# ESP8266to32.net
KiCad netlist of a schematic drawn in Altium Designer
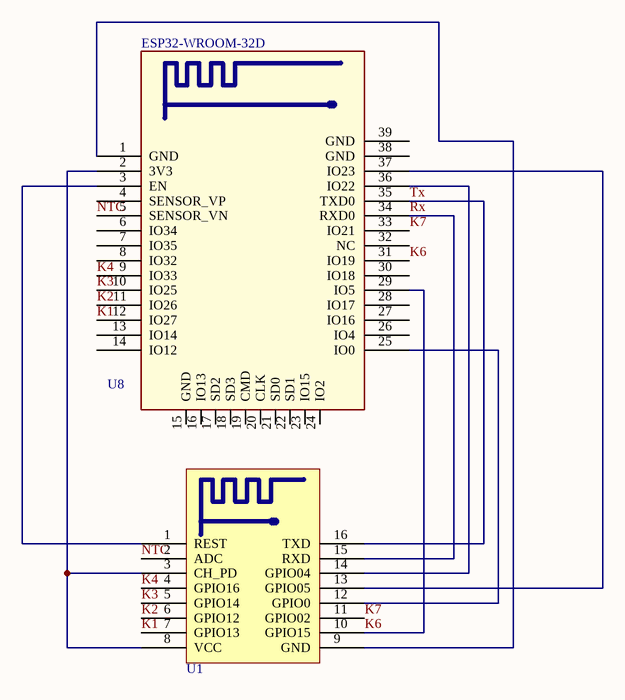
[diagram p0: ESP8266to32.SchDoc]

(export (version "E")
  (design (tool "Eeschema 10.0.6"))
  (components
    (comp (ref "U1") (value "ESP-8266") (footprint "ESP_12E") (libsource (lib "msb") (part "ESP-8266")))
    (comp (ref "U8")
      (value "ESP32-WROOM-32D")
      (footprint "esp32 WROOM-L")
      (description "IC: SoC; GPIO, I2C, I2S, IR, SD, SDIO, SPI, UART; 2.7Ã·3.6VDC; 20dBm")
      (fields (field (name "MF") "Espressif Systems"))
      (libsource (lib "msb") (part "ESP32-WROOM-32D"))
    )
  )
  (nets
    (net (code "1") (name "/K1") (class "Default")
      (node (ref "U1") (pin "7") (pinfunction "GPIO13_7") (pintype "passive"))
      (node (ref "U8") (pin "12") (pinfunction "IO27_12") (pintype "passive"))
    )
    (net (code "2") (name "/K2") (class "Default")
      (node (ref "U1") (pin "6") (pinfunction "GPIO12_6") (pintype "passive"))
      (node (ref "U8") (pin "11") (pinfunction "IO26_11") (pintype "passive"))
    )
    (net (code "3") (name "/K3") (class "Default")
      (node (ref "U1") (pin "5") (pinfunction "GPIO14_5") (pintype "passive"))
      (node (ref "U8") (pin "10") (pinfunction "IO25_10") (pintype "passive"))
    )
    (net (code "4") (name "/K4") (class "Default")
      (node (ref "U1") (pin "4") (pinfunction "GPIO16_4") (pintype "passive"))
      (node (ref "U8") (pin "9") (pinfunction "IO33_9") (pintype "passive"))
    )
    (net (code "5") (name "/K6") (class "Default")
      (node (ref "U1") (pin "10") (pinfunction "GPIO15_10") (pintype "passive"))
      (node (ref "U8") (pin "29") (pinfunction "IO5_29") (pintype "passive"))
      (node (ref "U8") (pin "31") (pinfunction "IO19_31") (pintype "passive"))
    )
    (net (code "6") (name "/K7") (class "Default")
      (node (ref "U1") (pin "11") (pinfunction "GPIO02_11") (pintype "passive"))
      (node (ref "U8") (pin "33") (pinfunction "IO21_33") (pintype "passive"))
    )
    (net (code "7") (name "/NTC") (class "Default")
      (node (ref "U1") (pin "2") (pinfunction "ADC_2") (pintype "passive"))
      (node (ref "U8") (pin "5") (pinfunction "SENSOR_VN_5") (pintype "passive"))
    )
    (net (code "8") (name "/Rx") (class "Default")
      (node (ref "U1") (pin "15") (pinfunction "RXD_15") (pintype "passive"))
      (node (ref "U8") (pin "34") (pinfunction "RXD0_34") (pintype "passive"))
    )
    (net (code "9") (name "/Tx") (class "Default")
      (node (ref "U1") (pin "16") (pinfunction "TXD_16") (pintype "passive"))
      (node (ref "U8") (pin "35") (pinfunction "TXD0_35") (pintype "passive"))
    )
    (net (code "10") (name "Net-(U1-CH_PD)") (class "Default")
      (node (ref "U1") (pin "3") (pinfunction "CH_PD_3") (pintype "passive"))
      (node (ref "U1") (pin "8") (pinfunction "VCC_8") (pintype "power_in"))
      (node (ref "U8") (pin "2") (pinfunction "3V3_2") (pintype "power_in"))
    )
    (net (code "11") (name "Net-(U1-GND)") (class "Default")
      (node (ref "U1") (pin "9") (pinfunction "GND_9") (pintype "power_in"))
      (node (ref "U8") (pin "1") (pinfunction "GND_1") (pintype "power_in"))
    )
    (net (code "12") (name "Net-(U1-GPIO0)") (class "Default")
      (node (ref "U1") (pin "12") (pinfunction "GPIO0_12") (pintype "passive"))
      (node (ref "U8") (pin "25") (pinfunction "IO0_25") (pintype "passive"))
    )
    (net (code "13") (name "Net-(U1-GPIO04)") (class "Default")
      (node (ref "U1") (pin "14") (pinfunction "GPIO04_14") (pintype "passive"))
      (node (ref "U8") (pin "36") (pinfunction "IO22_36") (pintype "passive"))
    )
    (net (code "14") (name "Net-(U1-GPIO05)") (class "Default")
      (node (ref "U1") (pin "13") (pinfunction "GPIO05_13") (pintype "passive"))
      (node (ref "U8") (pin "37") (pinfunction "IO23_37") (pintype "passive"))
    )
    (net (code "15") (name "Net-(U1-REST)") (class "Default")
      (node (ref "U1") (pin "1") (pinfunction "REST_1") (pintype "passive"))
      (node (ref "U8") (pin "3") (pinfunction "EN_3") (pintype "passive"))
    )
    (net (code "16") (name "unconnected-(U8-CLK-Pad20)") (class "Default")
      (node (ref "U8") (pin "20") (pinfunction "CLK_20") (pintype "passive"))
    )
    (net (code "17") (name "unconnected-(U8-CMD-Pad19)") (class "Default")
      (node (ref "U8") (pin "19") (pinfunction "CMD_19") (pintype "passive"))
    )
    (net (code "18") (name "unconnected-(U8-GND-Pad15)") (class "Default")
      (node (ref "U8") (pin "15") (pinfunction "GND_15") (pintype "power_in"))
    )
    (net (code "19") (name "unconnected-(U8-GND-Pad38)") (class "Default")
      (node (ref "U8") (pin "38") (pinfunction "GND_38") (pintype "passive"))
    )
    (net (code "20") (name "unconnected-(U8-GND-Pad39)") (class "Default")
      (node (ref "U8") (pin "39") (pinfunction "GND_39") (pintype "power_in"))
    )
    (net (code "21") (name "unconnected-(U8-IO2-Pad24)") (class "Default")
      (node (ref "U8") (pin "24") (pinfunction "IO2_24") (pintype "passive"))
    )
    (net (code "22") (name "unconnected-(U8-IO4-Pad26)") (class "Default")
      (node (ref "U8") (pin "26") (pinfunction "IO4_26") (pintype "passive"))
    )
    (net (code "23") (name "unconnected-(U8-IO12-Pad14)") (class "Default")
      (node (ref "U8") (pin "14") (pinfunction "IO12_14") (pintype "passive"))
    )
    (net (code "24") (name "unconnected-(U8-IO13-Pad16)") (class "Default")
      (node (ref "U8") (pin "16") (pinfunction "IO13_16") (pintype "passive"))
    )
    (net (code "25") (name "unconnected-(U8-IO14-Pad13)") (class "Default")
      (node (ref "U8") (pin "13") (pinfunction "IO14_13") (pintype "passive"))
    )
    (net (code "26") (name "unconnected-(U8-IO15-Pad23)") (class "Default")
      (node (ref "U8") (pin "23") (pinfunction "IO15_23") (pintype "passive"))
    )
    (net (code "27") (name "unconnected-(U8-IO16-Pad27)") (class "Default")
      (node (ref "U8") (pin "27") (pinfunction "IO16_27") (pintype "passive"))
    )
    (net (code "28") (name "unconnected-(U8-IO17-Pad28)") (class "Default")
      (node (ref "U8") (pin "28") (pinfunction "IO17_28") (pintype "passive"))
    )
    (net (code "29") (name "unconnected-(U8-IO18-Pad30)") (class "Default")
      (node (ref "U8") (pin "30") (pinfunction "IO18_30") (pintype "passive"))
    )
    (net (code "30") (name "unconnected-(U8-IO32-Pad8)") (class "Default")
      (node (ref "U8") (pin "8") (pinfunction "IO32_8") (pintype "passive"))
    )
    (net (code "31") (name "unconnected-(U8-IO34-Pad6)") (class "Default")
      (node (ref "U8") (pin "6") (pinfunction "IO34_6") (pintype "passive"))
    )
    (net (code "32") (name "unconnected-(U8-IO35-Pad7)") (class "Default")
      (node (ref "U8") (pin "7") (pinfunction "IO35_7") (pintype "passive"))
    )
    (net (code "33") (name "unconnected-(U8-NC-Pad32)") (class "Default")
      (node (ref "U8") (pin "32") (pinfunction "NC_32") (pintype "passive"))
    )
    (net (code "34") (name "unconnected-(U8-SD0-Pad21)") (class "Default")
      (node (ref "U8") (pin "21") (pinfunction "SD0_21") (pintype "passive"))
    )
    (net (code "35") (name "unconnected-(U8-SD1-Pad22)") (class "Default")
      (node (ref "U8") (pin "22") (pinfunction "SD1_22") (pintype "passive"))
    )
    (net (code "36") (name "unconnected-(U8-SD2-Pad17)") (class "Default")
      (node (ref "U8") (pin "17") (pinfunction "SD2_17") (pintype "passive"))
    )
    (net (code "37") (name "unconnected-(U8-SD3-Pad18)") (class "Default")
      (node (ref "U8") (pin "18") (pinfunction "SD3_18") (pintype "passive"))
    )
    (net (code "38") (name "unconnected-(U8-SENSOR_VP-Pad4)") (class "Default")
      (node (ref "U8") (pin "4") (pinfunction "SENSOR_VP_4") (pintype "passive"))
    )
  )
)
